# GAIN_SCH.net
KiCad netlist of a schematic drawn in EAGLE
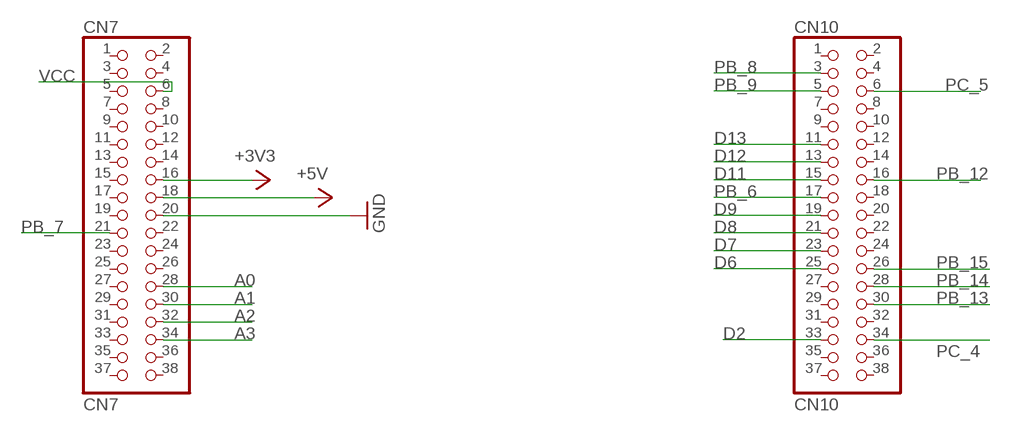
[diagram p0: schematic, sheet 1]
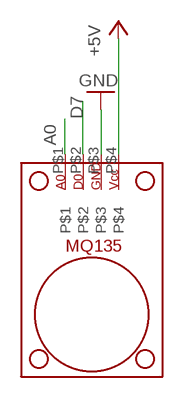
[diagram p1: schematic, sheet 2]
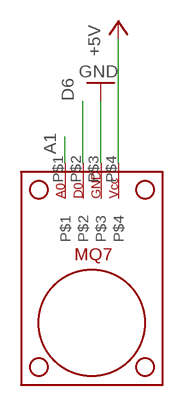
[diagram p2: schematic, sheet 3]
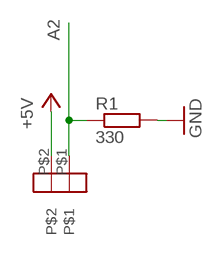
[diagram p3: schematic, sheet 4]
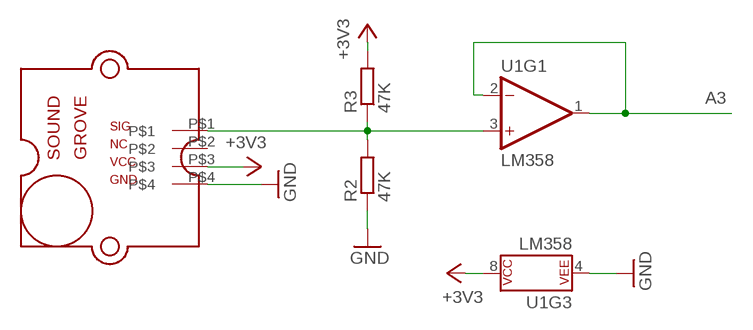
[diagram p4: schematic, sheet 5]
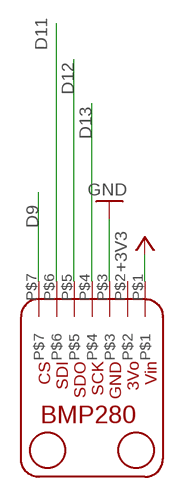
[diagram p5: schematic, sheet 6]
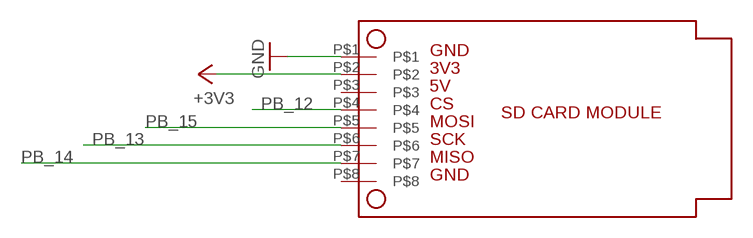
[diagram p6: schematic, sheet 7]
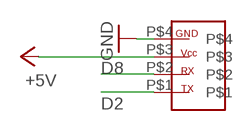
[diagram p7: schematic, sheet 8]
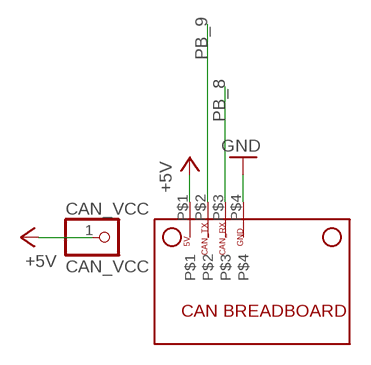
[diagram p8: schematic, sheet 9]
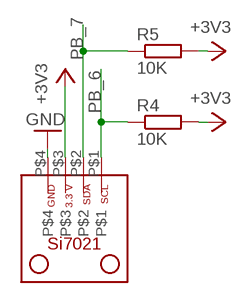
[diagram p9: schematic, sheet 10]
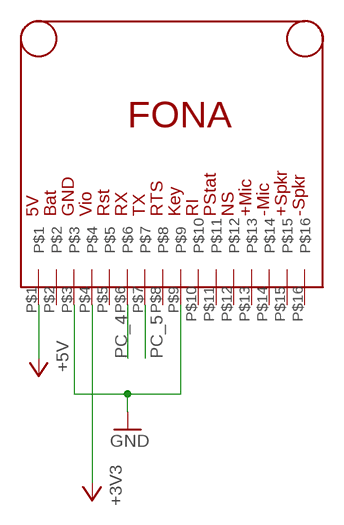
[diagram p10: schematic, sheet 11]
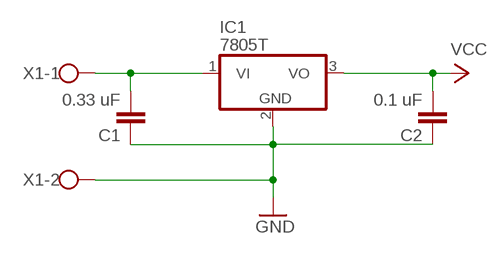
[diagram p11: schematic, sheet 12]

(export (version "E")
  (design (tool "Eeschema 10.0.6"))
  (components
    (comp (ref "U$6")
      (value "SD_CARD")
      (footprint "eagle-import:SD_CARD")
      (libsource (lib "eagle-import") (part "SD_CARD"))
    )
    (comp (ref "U$10")
      (value "CO2_GROVE")
      (footprint "eagle-import:CO2_GROVE")
      (libsource (lib "eagle-import") (part "CO2_GROVE"))
    )
    (comp (ref "R2")
      (value "47K")
      (footprint "eagle-import:0207_10")
      (libsource (lib "eagle-import") (part "R-EU_0207/10"))
    )
    (comp (ref "R3")
      (value "47K")
      (footprint "eagle-import:0207_10")
      (libsource (lib "eagle-import") (part "R-EU_0207/10"))
    )
    (comp (ref "U$4")
      (value "GROVE_SOUND")
      (footprint "eagle-import:GROVE_SOUND")
      (libsource (lib "eagle-import") (part "GROVE_SOUND"))
    )
    (comp (ref "U1")
      (value "LM358")
      (footprint "eagle-import:DIP08")
      (libsource (lib "eagle-import") (part "LM358"))
    )
    (comp (ref "U$2")
      (value "MQ7")
      (footprint "eagle-import:MQ7")
      (libsource (lib "eagle-import") (part "MQ7"))
    )
    (comp (ref "CN7")
      (value "CN7")
      (footprint "eagle-import:2X19")
      (libsource (lib "eagle-import") (part "PINHD-2X19"))
    )
    (comp (ref "CN10")
      (value "CN10")
      (footprint "eagle-import:2X19")
      (libsource (lib "eagle-import") (part "PINHD-2X19"))
    )
    (comp (ref "U$9")
      (value "FONA")
      (footprint "eagle-import:FONA")
      (libsource (lib "eagle-import") (part "FONA"))
    )
    (comp (ref "R4")
      (value "10K")
      (footprint "eagle-import:0207_10")
      (libsource (lib "eagle-import") (part "R-EU_0207/10"))
    )
    (comp (ref "R5")
      (value "10K")
      (footprint "eagle-import:0207_10")
      (libsource (lib "eagle-import") (part "R-EU_0207/10"))
    )
    (comp (ref "U$8")
      (value "SI7021")
      (footprint "eagle-import:SI7021")
      (libsource (lib "eagle-import") (part "SI7021"))
    )
    (comp (ref "R1")
      (value "330")
      (footprint "eagle-import:0207_10")
      (libsource (lib "eagle-import") (part "R-EU_0207/10"))
    )
    (comp (ref "U$3")
      (value "LDR")
      (footprint "eagle-import:LDR")
      (libsource (lib "eagle-import") (part "LDR"))
    )
    (comp (ref "U$1")
      (value "MQ135")
      (footprint "eagle-import:MQ135")
      (libsource (lib "eagle-import") (part "MQ135"))
    )
    (comp (ref "CAN_VCC")
      (value "CAN_VCC")
      (footprint "eagle-import:1X01")
      (libsource (lib "eagle-import") (part "PINHD-1X1"))
    )
    (comp (ref "U$7")
      (value "CAN_BREADBOARD")
      (footprint "eagle-import:CAN_BREAKBOARD")
      (libsource (lib "eagle-import") (part "CAN_BREADBOARD"))
    )
    (comp (ref "C1")
      (value "0.33 uF")
      (footprint "eagle-import:C050-030X075")
      (libsource (lib "eagle-import") (part "C-EU050-030X075"))
    )
    (comp (ref "C2")
      (value "0.1 uF")
      (footprint "eagle-import:C050-030X075")
      (libsource (lib "eagle-import") (part "C-EU050-030X075"))
    )
    (comp (ref "IC1")
      (value "7805T")
      (footprint "eagle-import:TO220H")
      (libsource (lib "eagle-import") (part "78T05"))
    )
    (comp (ref "X1")
      (value "W237-102")
      (footprint "eagle-import:W237-102")
      (fields (field (name "MPN") "237-102"))
      (libsource (lib "eagle-import") (part "W237-102"))
    )
    (comp (ref "U$5")
      (value "BMP280")
      (footprint "eagle-import:BMP280")
      (libsource (lib "eagle-import") (part "BMP280"))
    )
  )
  (nets
    (net (code "1") (name "+3V3") (class "Default")
      (node (ref "CN7") (pin "16") (pinfunction "16_16") (pintype "passive"))
      (node (ref "R3") (pin "2") (pinfunction "2_2") (pintype "passive"))
      (node (ref "R4") (pin "2") (pinfunction "2_2") (pintype "passive"))
      (node (ref "R5") (pin "2") (pinfunction "2_2") (pintype "passive"))
      (node (ref "U$4") (pin "P$3") (pinfunction "P$3_P$3") (pintype "bidirectional"))
      (node (ref "U$5") (pin "P$1") (pinfunction "P$1_P$1") (pintype "bidirectional"))
      (node (ref "U$6") (pin "P$2") (pinfunction "P$2_P$2") (pintype "bidirectional"))
      (node (ref "U$8") (pin "P$3") (pinfunction "P$3_P$3") (pintype "bidirectional"))
      (node (ref "U$9") (pin "P$4") (pinfunction "P$4_P$4") (pintype "bidirectional"))
      (node (ref "U1") (pin "8") (pinfunction "P$V+_8") (pintype "bidirectional"))
    )
    (net (code "2") (name "+5V") (class "Default")
      (node (ref "CAN_VCC") (pin "1") (pinfunction "1_1") (pintype "passive"))
      (node (ref "CN7") (pin "18") (pinfunction "18_18") (pintype "passive"))
      (node (ref "U$1") (pin "P$4") (pinfunction "P$4_P$4") (pintype "bidirectional"))
      (node (ref "U$10") (pin "P$3") (pinfunction "P$3_P$3") (pintype "bidirectional"))
      (node (ref "U$2") (pin "P$4") (pinfunction "P$4_P$4") (pintype "bidirectional"))
      (node (ref "U$3") (pin "P$2") (pinfunction "P$2_P$2") (pintype "bidirectional"))
      (node (ref "U$7") (pin "P$1") (pinfunction "P$1_P$1") (pintype "bidirectional"))
      (node (ref "U$9") (pin "P$1") (pinfunction "P$1_P$1") (pintype "bidirectional"))
    )
    (net (code "3") (name "A0") (class "Default")
      (node (ref "CN7") (pin "28") (pinfunction "28_28") (pintype "passive"))
      (node (ref "U$1") (pin "P$1") (pinfunction "P$1_P$1") (pintype "bidirectional"))
    )
    (net (code "4") (name "A1") (class "Default")
      (node (ref "CN7") (pin "30") (pinfunction "30_30") (pintype "passive"))
      (node (ref "U$2") (pin "P$1") (pinfunction "P$1_P$1") (pintype "bidirectional"))
    )
    (net (code "5") (name "A2") (class "Default")
      (node (ref "CN7") (pin "32") (pinfunction "32_32") (pintype "passive"))
      (node (ref "R1") (pin "1") (pinfunction "1_1") (pintype "passive"))
      (node (ref "U$3") (pin "P$1") (pinfunction "P$1_P$1") (pintype "bidirectional"))
    )
    (net (code "6") (name "A3") (class "Default")
      (node (ref "CN7") (pin "34") (pinfunction "34_34") (pintype "passive"))
      (node (ref "U1") (pin "1") (pinfunction "OUT_1") (pintype "output"))
      (node (ref "U1") (pin "2") (pinfunction "-IN_2") (pintype "input"))
    )
    (net (code "7") (name "D2") (class "Default")
      (node (ref "CN10") (pin "33") (pinfunction "33_33") (pintype "passive"))
      (node (ref "U$10") (pin "P$1") (pinfunction "P$1_P$1") (pintype "bidirectional"))
    )
    (net (code "8") (name "D6") (class "Default")
      (node (ref "CN10") (pin "25") (pinfunction "25_25") (pintype "passive"))
      (node (ref "U$2") (pin "P$2") (pinfunction "P$2_P$2") (pintype "bidirectional"))
    )
    (net (code "9") (name "D7") (class "Default")
      (node (ref "CN10") (pin "23") (pinfunction "23_23") (pintype "passive"))
      (node (ref "U$1") (pin "P$2") (pinfunction "P$2_P$2") (pintype "bidirectional"))
    )
    (net (code "10") (name "D8") (class "Default")
      (node (ref "CN10") (pin "21") (pinfunction "21_21") (pintype "passive"))
      (node (ref "U$10") (pin "P$2") (pinfunction "P$2_P$2") (pintype "bidirectional"))
    )
    (net (code "11") (name "D9") (class "Default")
      (node (ref "CN10") (pin "19") (pinfunction "19_19") (pintype "passive"))
      (node (ref "U$5") (pin "P$7") (pinfunction "P$7_P$7") (pintype "bidirectional"))
    )
    (net (code "12") (name "D11") (class "Default")
      (node (ref "CN10") (pin "15") (pinfunction "15_15") (pintype "passive"))
      (node (ref "U$5") (pin "P$6") (pinfunction "P$6_P$6") (pintype "bidirectional"))
    )
    (net (code "13") (name "D12") (class "Default")
      (node (ref "CN10") (pin "13") (pinfunction "13_13") (pintype "passive"))
      (node (ref "U$5") (pin "P$5") (pinfunction "P$5_P$5") (pintype "bidirectional"))
    )
    (net (code "14") (name "D13") (class "Default")
      (node (ref "CN10") (pin "11") (pinfunction "11_11") (pintype "passive"))
      (node (ref "U$5") (pin "P$4") (pinfunction "P$4_P$4") (pintype "bidirectional"))
    )
    (net (code "15") (name "GND") (class "Default")
      (node (ref "C1") (pin "1") (pinfunction "1_1") (pintype "passive"))
      (node (ref "C2") (pin "1") (pinfunction "1_1") (pintype "passive"))
      (node (ref "CN7") (pin "20") (pinfunction "20_20") (pintype "passive"))
      (node (ref "IC1") (pin "2") (pinfunction "GND_2") (pintype "passive"))
      (node (ref "R1") (pin "2") (pinfunction "2_2") (pintype "passive"))
      (node (ref "R2") (pin "1") (pinfunction "1_1") (pintype "passive"))
      (node (ref "U$1") (pin "P$3") (pinfunction "P$3_P$3") (pintype "bidirectional"))
      (node (ref "U$10") (pin "P$4") (pinfunction "P$4_P$4") (pintype "bidirectional"))
      (node (ref "U$2") (pin "P$3") (pinfunction "P$3_P$3") (pintype "bidirectional"))
      (node (ref "U$4") (pin "P$4") (pinfunction "P$4_P$4") (pintype "bidirectional"))
      (node (ref "U$5") (pin "P$3") (pinfunction "P$3_P$3") (pintype "bidirectional"))
      (node (ref "U$6") (pin "P$1") (pinfunction "P$1_P$1") (pintype "bidirectional"))
      (node (ref "U$7") (pin "P$4") (pinfunction "P$4_P$4") (pintype "bidirectional"))
      (node (ref "U$8") (pin "P$4") (pinfunction "P$4_P$4") (pintype "bidirectional"))
      (node (ref "U$9") (pin "P$3") (pinfunction "P$3_P$3") (pintype "bidirectional"))
      (node (ref "U$9") (pin "P$9") (pinfunction "P$9_P$9") (pintype "bidirectional"))
      (node (ref "U1") (pin "4") (pinfunction "P$V-_4") (pintype "bidirectional"))
      (node (ref "X1") (pin "2") (pinfunction "KL_2") (pintype "passive"))
    )
    (net (code "16") (name "Net-(IC1-VI)") (class "Default")
      (node (ref "C1") (pin "2") (pinfunction "2_2") (pintype "passive"))
      (node (ref "IC1") (pin "1") (pinfunction "VI_1") (pintype "input"))
      (node (ref "X1") (pin "1") (pinfunction "KL_1") (pintype "passive"))
    )
    (net (code "17") (name "Net-(U1A-+IN)") (class "Default")
      (node (ref "R2") (pin "2") (pinfunction "2_2") (pintype "passive"))
      (node (ref "R3") (pin "1") (pinfunction "1_1") (pintype "passive"))
      (node (ref "U$4") (pin "P$1") (pinfunction "P$1_P$1") (pintype "bidirectional"))
      (node (ref "U1") (pin "3") (pinfunction "+IN_3") (pintype "input"))
    )
    (net (code "18") (name "PB_6") (class "Default")
      (node (ref "CN10") (pin "17") (pinfunction "17_17") (pintype "passive"))
      (node (ref "R4") (pin "1") (pinfunction "1_1") (pintype "passive"))
      (node (ref "U$8") (pin "P$1") (pinfunction "P$1_P$1") (pintype "bidirectional"))
    )
    (net (code "19") (name "PB_7") (class "Default")
      (node (ref "CN7") (pin "21") (pinfunction "21_21") (pintype "passive"))
      (node (ref "R5") (pin "1") (pinfunction "1_1") (pintype "passive"))
      (node (ref "U$8") (pin "P$2") (pinfunction "P$2_P$2") (pintype "bidirectional"))
    )
    (net (code "20") (name "PB_8") (class "Default")
      (node (ref "CN10") (pin "3") (pinfunction "3_3") (pintype "passive"))
      (node (ref "U$7") (pin "P$3") (pinfunction "P$3_P$3") (pintype "bidirectional"))
    )
    (net (code "21") (name "PB_9") (class "Default")
      (node (ref "CN10") (pin "5") (pinfunction "5_5") (pintype "passive"))
      (node (ref "U$7") (pin "P$2") (pinfunction "P$2_P$2") (pintype "bidirectional"))
    )
    (net (code "22") (name "PB_12") (class "Default")
      (node (ref "CN10") (pin "16") (pinfunction "16_16") (pintype "passive"))
      (node (ref "U$6") (pin "P$4") (pinfunction "P$4_P$4") (pintype "bidirectional"))
    )
    (net (code "23") (name "PB_13") (class "Default")
      (node (ref "CN10") (pin "30") (pinfunction "30_30") (pintype "passive"))
      (node (ref "U$6") (pin "P$6") (pinfunction "P$6_P$6") (pintype "bidirectional"))
    )
    (net (code "24") (name "PB_14") (class "Default")
      (node (ref "CN10") (pin "28") (pinfunction "28_28") (pintype "passive"))
      (node (ref "U$6") (pin "P$7") (pinfunction "P$7_P$7") (pintype "bidirectional"))
    )
    (net (code "25") (name "PB_15") (class "Default")
      (node (ref "CN10") (pin "26") (pinfunction "26_26") (pintype "passive"))
      (node (ref "U$6") (pin "P$5") (pinfunction "P$5_P$5") (pintype "bidirectional"))
    )
    (net (code "26") (name "PC_4") (class "Default")
      (node (ref "CN10") (pin "34") (pinfunction "34_34") (pintype "passive"))
      (node (ref "U$9") (pin "P$6") (pinfunction "P$6_P$6") (pintype "bidirectional"))
    )
    (net (code "27") (name "PC_5") (class "Default")
      (node (ref "CN10") (pin "6") (pinfunction "6_6") (pintype "passive"))
      (node (ref "U$9") (pin "P$7") (pinfunction "P$7_P$7") (pintype "bidirectional"))
    )
    (net (code "28") (name "VCC") (class "Default")
      (node (ref "C2") (pin "2") (pinfunction "2_2") (pintype "passive"))
      (node (ref "CN7") (pin "6") (pinfunction "6_6") (pintype "passive"))
      (node (ref "IC1") (pin "3") (pinfunction "VO_3") (pintype "passive"))
    )
    (net (code "29") (name "unconnected-(CN7-Pad1)") (class "Default")
      (node (ref "CN7") (pin "1") (pinfunction "1_1") (pintype "passive"))
    )
    (net (code "30") (name "unconnected-(CN7-Pad2)") (class "Default")
      (node (ref "CN7") (pin "2") (pinfunction "2_2") (pintype "passive"))
    )
    (net (code "31") (name "unconnected-(CN7-Pad3)") (class "Default")
      (node (ref "CN7") (pin "3") (pinfunction "3_3") (pintype "passive"))
    )
    (net (code "32") (name "unconnected-(CN7-Pad4)") (class "Default")
      (node (ref "CN7") (pin "4") (pinfunction "4_4") (pintype "passive"))
    )
    (net (code "33") (name "unconnected-(CN7-Pad5)") (class "Default")
      (node (ref "CN7") (pin "5") (pinfunction "5_5") (pintype "passive"))
    )
    (net (code "34") (name "unconnected-(CN7-Pad7)") (class "Default")
      (node (ref "CN7") (pin "7") (pinfunction "7_7") (pintype "passive"))
    )
    (net (code "35") (name "unconnected-(CN7-Pad8)") (class "Default")
      (node (ref "CN7") (pin "8") (pinfunction "8_8") (pintype "passive"))
    )
    (net (code "36") (name "unconnected-(CN7-Pad9)") (class "Default")
      (node (ref "CN7") (pin "9") (pinfunction "9_9") (pintype "passive"))
    )
    (net (code "37") (name "unconnected-(CN7-Pad10)") (class "Default")
      (node (ref "CN7") (pin "10") (pinfunction "10_10") (pintype "passive"))
    )
    (net (code "38") (name "unconnected-(CN7-Pad11)") (class "Default")
      (node (ref "CN7") (pin "11") (pinfunction "11_11") (pintype "passive"))
    )
    (net (code "39") (name "unconnected-(CN7-Pad12)") (class "Default")
      (node (ref "CN7") (pin "12") (pinfunction "12_12") (pintype "passive"))
    )
    (net (code "40") (name "unconnected-(CN7-Pad13)") (class "Default")
      (node (ref "CN7") (pin "13") (pinfunction "13_13") (pintype "passive"))
    )
    (net (code "41") (name "unconnected-(CN7-Pad14)") (class "Default")
      (node (ref "CN7") (pin "14") (pinfunction "14_14") (pintype "passive"))
    )
    (net (code "42") (name "unconnected-(CN7-Pad15)") (class "Default")
      (node (ref "CN7") (pin "15") (pinfunction "15_15") (pintype "passive"))
    )
    (net (code "43") (name "unconnected-(CN7-Pad17)") (class "Default")
      (node (ref "CN7") (pin "17") (pinfunction "17_17") (pintype "passive"))
    )
    (net (code "44") (name "unconnected-(CN7-Pad19)") (class "Default")
      (node (ref "CN7") (pin "19") (pinfunction "19_19") (pintype "passive"))
    )
    (net (code "45") (name "unconnected-(CN7-Pad22)") (class "Default")
      (node (ref "CN7") (pin "22") (pinfunction "22_22") (pintype "passive"))
    )
    (net (code "46") (name "unconnected-(CN7-Pad23)") (class "Default")
      (node (ref "CN7") (pin "23") (pinfunction "23_23") (pintype "passive"))
    )
    (net (code "47") (name "unconnected-(CN7-Pad24)") (class "Default")
      (node (ref "CN7") (pin "24") (pinfunction "24_24") (pintype "passive"))
    )
    (net (code "48") (name "unconnected-(CN7-Pad25)") (class "Default")
      (node (ref "CN7") (pin "25") (pinfunction "25_25") (pintype "passive"))
    )
    (net (code "49") (name "unconnected-(CN7-Pad26)") (class "Default")
      (node (ref "CN7") (pin "26") (pinfunction "26_26") (pintype "passive"))
    )
    (net (code "50") (name "unconnected-(CN7-Pad27)") (class "Default")
      (node (ref "CN7") (pin "27") (pinfunction "27_27") (pintype "passive"))
    )
    (net (code "51") (name "unconnected-(CN7-Pad29)") (class "Default")
      (node (ref "CN7") (pin "29") (pinfunction "29_29") (pintype "passive"))
    )
    (net (code "52") (name "unconnected-(CN7-Pad31)") (class "Default")
      (node (ref "CN7") (pin "31") (pinfunction "31_31") (pintype "passive"))
    )
    (net (code "53") (name "unconnected-(CN7-Pad33)") (class "Default")
      (node (ref "CN7") (pin "33") (pinfunction "33_33") (pintype "passive"))
    )
    (net (code "54") (name "unconnected-(CN7-Pad35)") (class "Default")
      (node (ref "CN7") (pin "35") (pinfunction "35_35") (pintype "passive"))
    )
    (net (code "55") (name "unconnected-(CN7-Pad36)") (class "Default")
      (node (ref "CN7") (pin "36") (pinfunction "36_36") (pintype "passive"))
    )
    (net (code "56") (name "unconnected-(CN7-Pad37)") (class "Default")
      (node (ref "CN7") (pin "37") (pinfunction "37_37") (pintype "passive"))
    )
    (net (code "57") (name "unconnected-(CN7-Pad38)") (class "Default")
      (node (ref "CN7") (pin "38") (pinfunction "38_38") (pintype "passive"))
    )
    (net (code "58") (name "unconnected-(CN10-Pad1)") (class "Default")
      (node (ref "CN10") (pin "1") (pinfunction "1_1") (pintype "passive"))
    )
    (net (code "59") (name "unconnected-(CN10-Pad2)") (class "Default")
      (node (ref "CN10") (pin "2") (pinfunction "2_2") (pintype "passive"))
    )
    (net (code "60") (name "unconnected-(CN10-Pad4)") (class "Default")
      (node (ref "CN10") (pin "4") (pinfunction "4_4") (pintype "passive"))
    )
    (net (code "61") (name "unconnected-(CN10-Pad7)") (class "Default")
      (node (ref "CN10") (pin "7") (pinfunction "7_7") (pintype "passive"))
    )
    (net (code "62") (name "unconnected-(CN10-Pad8)") (class "Default")
      (node (ref "CN10") (pin "8") (pinfunction "8_8") (pintype "passive"))
    )
    (net (code "63") (name "unconnected-(CN10-Pad9)") (class "Default")
      (node (ref "CN10") (pin "9") (pinfunction "9_9") (pintype "passive"))
    )
    (net (code "64") (name "unconnected-(CN10-Pad10)") (class "Default")
      (node (ref "CN10") (pin "10") (pinfunction "10_10") (pintype "passive"))
    )
    (net (code "65") (name "unconnected-(CN10-Pad12)") (class "Default")
      (node (ref "CN10") (pin "12") (pinfunction "12_12") (pintype "passive"))
    )
    (net (code "66") (name "unconnected-(CN10-Pad14)") (class "Default")
      (node (ref "CN10") (pin "14") (pinfunction "14_14") (pintype "passive"))
    )
    (net (code "67") (name "unconnected-(CN10-Pad18)") (class "Default")
      (node (ref "CN10") (pin "18") (pinfunction "18_18") (pintype "passive"))
    )
    (net (code "68") (name "unconnected-(CN10-Pad20)") (class "Default")
      (node (ref "CN10") (pin "20") (pinfunction "20_20") (pintype "passive"))
    )
    (net (code "69") (name "unconnected-(CN10-Pad22)") (class "Default")
      (node (ref "CN10") (pin "22") (pinfunction "22_22") (pintype "passive"))
    )
    (net (code "70") (name "unconnected-(CN10-Pad24)") (class "Default")
      (node (ref "CN10") (pin "24") (pinfunction "24_24") (pintype "passive"))
    )
    (net (code "71") (name "unconnected-(CN10-Pad27)") (class "Default")
      (node (ref "CN10") (pin "27") (pinfunction "27_27") (pintype "passive"))
    )
    (net (code "72") (name "unconnected-(CN10-Pad29)") (class "Default")
      (node (ref "CN10") (pin "29") (pinfunction "29_29") (pintype "passive"))
    )
    (net (code "73") (name "unconnected-(CN10-Pad31)") (class "Default")
      (node (ref "CN10") (pin "31") (pinfunction "31_31") (pintype "passive"))
    )
    (net (code "74") (name "unconnected-(CN10-Pad32)") (class "Default")
      (node (ref "CN10") (pin "32") (pinfunction "32_32") (pintype "passive"))
    )
    (net (code "75") (name "unconnected-(CN10-Pad35)") (class "Default")
      (node (ref "CN10") (pin "35") (pinfunction "35_35") (pintype "passive"))
    )
    (net (code "76") (name "unconnected-(CN10-Pad36)") (class "Default")
      (node (ref "CN10") (pin "36") (pinfunction "36_36") (pintype "passive"))
    )
    (net (code "77") (name "unconnected-(CN10-Pad37)") (class "Default")
      (node (ref "CN10") (pin "37") (pinfunction "37_37") (pintype "passive"))
    )
    (net (code "78") (name "unconnected-(CN10-Pad38)") (class "Default")
      (node (ref "CN10") (pin "38") (pinfunction "38_38") (pintype "passive"))
    )
    (net (code "79") (name "unconnected-(U$4-PadP$2)") (class "Default")
      (node (ref "U$4") (pin "P$2") (pinfunction "P$2_P$2") (pintype "bidirectional"))
    )
    (net (code "80") (name "unconnected-(U$5-PadP$2)") (class "Default")
      (node (ref "U$5") (pin "P$2") (pinfunction "P$2_P$2") (pintype "bidirectional"))
    )
    (net (code "81") (name "unconnected-(U$6-PadP$3)") (class "Default")
      (node (ref "U$6") (pin "P$3") (pinfunction "P$3_P$3") (pintype "bidirectional"))
    )
    (net (code "82") (name "unconnected-(U$6-PadP$8)") (class "Default")
      (node (ref "U$6") (pin "P$8") (pinfunction "P$8_P$8") (pintype "bidirectional"))
    )
    (net (code "83") (name "unconnected-(U$9-PadP$2)") (class "Default")
      (node (ref "U$9") (pin "P$2") (pinfunction "P$2_P$2") (pintype "bidirectional"))
    )
    (net (code "84") (name "unconnected-(U$9-PadP$5)") (class "Default")
      (node (ref "U$9") (pin "P$5") (pinfunction "P$5_P$5") (pintype "bidirectional"))
    )
    (net (code "85") (name "unconnected-(U$9-PadP$8)") (class "Default")
      (node (ref "U$9") (pin "P$8") (pinfunction "P$8_P$8") (pintype "bidirectional"))
    )
    (net (code "86") (name "unconnected-(U$9-PadP$10)") (class "Default")
      (node (ref "U$9") (pin "P$10") (pinfunction "P$10_P$10") (pintype "bidirectional"))
    )
    (net (code "87") (name "unconnected-(U$9-PadP$11)") (class "Default")
      (node (ref "U$9") (pin "P$11") (pinfunction "P$11_P$11") (pintype "bidirectional"))
    )
    (net (code "88") (name "unconnected-(U$9-PadP$12)") (class "Default")
      (node (ref "U$9") (pin "P$12") (pinfunction "P$12_P$12") (pintype "bidirectional"))
    )
    (net (code "89") (name "unconnected-(U$9-PadP$13)") (class "Default")
      (node (ref "U$9") (pin "P$13") (pinfunction "P$13_P$13") (pintype "bidirectional"))
    )
    (net (code "90") (name "unconnected-(U$9-PadP$14)") (class "Default")
      (node (ref "U$9") (pin "P$14") (pinfunction "P$14_P$14") (pintype "bidirectional"))
    )
    (net (code "91") (name "unconnected-(U$9-PadP$15)") (class "Default")
      (node (ref "U$9") (pin "P$15") (pinfunction "P$15_P$15") (pintype "bidirectional"))
    )
    (net (code "92") (name "unconnected-(U$9-PadP$16)") (class "Default")
      (node (ref "U$9") (pin "P$16") (pinfunction "P$16_P$16") (pintype "bidirectional"))
    )
  )
)
